# Amplifier.net
KiCad netlist of a schematic drawn in Altium Designer
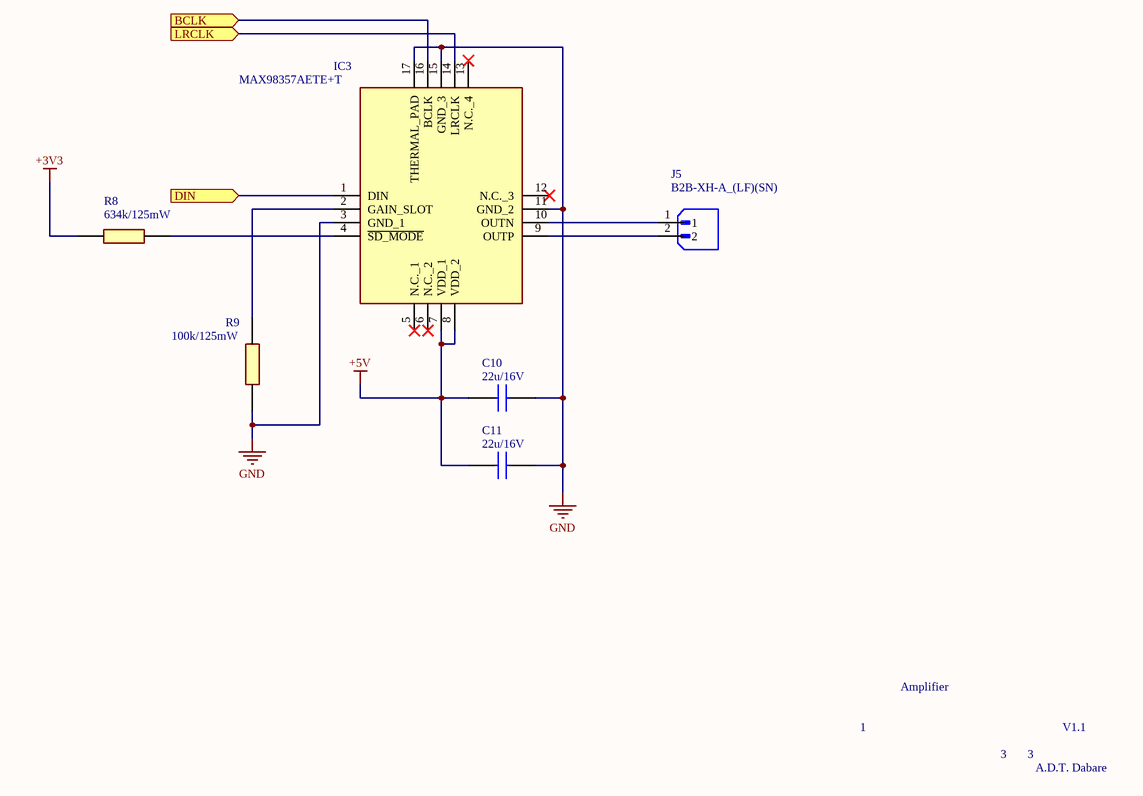
[diagram p0: Amplifier.SchDoc]

(export (version "E")
  (design (tool "Eeschema 10.0.6"))
  (components
    (comp (ref "C10")
      (value "22u/16V")
      (footprint "SamacSys:C0805")
      (description "Multilayer Ceramic Capacitors MLCC - SMD/SMT 16V 0.1uF X7R 0805 10% Flex AEC-Q200")
      (fields
        (field (name "MANUFACTURER_PART_NUMBER") "C0805X104K4RACAUTO")
        (field (name "MOUSER PART NUMBER") "80-C0805X104K4RAUTO")
      )
      (libsource (lib "*") (part "C0805X104K4RACAUTO"))
    )
    (comp (ref "C11")
      (value "22u/16V")
      (footprint "SamacSys:CAPC2012X94N")
      (fields
        (field (name "MANUFACTURER_PART_NUMBER") "0805YC106KAT2A")
        (field (name "MOUSER PART NUMBER") "581-0805YC106KAT2A")
      )
      (libsource (lib "*") (part "0805YC106KAT2A"))
    )
    (comp (ref "IC3")
      (value "MAX98357AETE+T")
      (footprint "SamacSys:QFN50P300X300X80-17N")
      (description "Audio Amplifiers Digital Input Class D Amplifier")
      (fields (field (name "MOUSER PART NUMBER") "700-MAX98357AETE+T"))
      (libsource (lib "*") (part "MAX98357AETE+T"))
    )
    (comp (ref "J5")
      (value "B2B-XH-A_(LF)(SN)")
      (footprint "JST_B2B-XH-A_(LF)(SN)")
      (description "Connector Header Through Hole 2 position 0.098 (2.50mm)")
      (fields (field (name "MF") "JST Sales") (field (name "MP") "B2B-XH-A (LF)(SN)"))
      (libsource (lib "B2B-XH-A__LF__SN_") (part "B2B-XH-A_(LF)(SN)"))
    )
    (comp (ref "R8")
      (value "634k/125mW")
      (footprint "SamacSys:RESC2012X50N")
      (description "Thick Film Resistors - SMD 1/8watt 634Kohms 1%")
      (fields
        (field (name "MANUFACTURER_PART_NUMBER") "CRCW0805634KFKEA")
        (field (name "MOUSER PART NUMBER") "71-CRCW0805634KFKEA")
      )
      (libsource (lib "*") (part "CRCW0805634KFKEA"))
    )
    (comp (ref "R9")
      (value "100k/125mW")
      (footprint "SamacSys:ERA6AEB101V")
      (description "Thin Film Resistors - SMD 0805 100Kohms 25ppm 0.5% AEC-Q200")
      (fields
        (field (name "MANUFACTURER_PART_NUMBER") "ERA-6AED104V")
        (field (name "MOUSER PART NUMBER") "667-ERA-6AED104V")
      )
      (libsource (lib "*") (part "ERA-6AED104V"))
    )
  )
  (nets
    (net (code "1") (name "+3V3") (class "Default")
      (node (ref "R8") (pin "1") (pinfunction "1_1") (pintype "passive"))
    )
    (net (code "2") (name "+5V") (class "Default")
      (node (ref "C10") (pin "1") (pinfunction "1_1") (pintype "passive"))
      (node (ref "C11") (pin "1") (pinfunction "1_1") (pintype "passive"))
      (node (ref "IC3") (pin "7") (pinfunction "VDD_1_7") (pintype "passive"))
      (node (ref "IC3") (pin "8") (pinfunction "VDD_2_8") (pintype "passive"))
    )
    (net (code "3") (name "/BCLK") (class "Default")
      (node (ref "IC3") (pin "16") (pinfunction "BCLK_16") (pintype "passive"))
    )
    (net (code "4") (name "/DIN") (class "Default")
      (node (ref "IC3") (pin "1") (pinfunction "DIN_1") (pintype "passive"))
    )
    (net (code "5") (name "/LRCLK") (class "Default")
      (node (ref "IC3") (pin "14") (pinfunction "LRCLK_14") (pintype "passive"))
    )
    (net (code "6") (name "GND") (class "Default")
      (node (ref "C10") (pin "2") (pinfunction "2_2") (pintype "passive"))
      (node (ref "C11") (pin "2") (pinfunction "2_2") (pintype "passive"))
      (node (ref "IC3") (pin "11") (pinfunction "GND_2_11") (pintype "passive"))
      (node (ref "IC3") (pin "15") (pinfunction "GND_3_15") (pintype "passive"))
      (node (ref "IC3") (pin "17") (pinfunction "THERMAL_PAD_17") (pintype "passive"))
      (node (ref "IC3") (pin "3") (pinfunction "GND_1_3") (pintype "passive"))
      (node (ref "R9") (pin "1") (pinfunction "1_1") (pintype "passive"))
    )
    (net (code "7") (name "Net-(IC3-GAIN_SLOT)") (class "Default")
      (node (ref "IC3") (pin "2") (pinfunction "GAIN_SLOT_2") (pintype "passive"))
      (node (ref "R9") (pin "2") (pinfunction "2_2") (pintype "passive"))
    )
    (net (code "8") (name "Net-(IC3-OUTN)") (class "Default")
      (node (ref "IC3") (pin "10") (pinfunction "OUTN_10") (pintype "passive"))
      (node (ref "J5") (pin "1") (pinfunction "1_1") (pintype "passive"))
    )
    (net (code "9") (name "Net-(IC3-OUTP)") (class "Default")
      (node (ref "IC3") (pin "9") (pinfunction "OUTP_9") (pintype "passive"))
      (node (ref "J5") (pin "2") (pinfunction "2_2") (pintype "passive"))
    )
    (net (code "10") (name "Net-(IC3-~{SD_MODE})") (class "Default")
      (node (ref "IC3") (pin "4") (pinfunction "~{SD_MODE}_4") (pintype "passive"))
      (node (ref "R8") (pin "2") (pinfunction "2_2") (pintype "passive"))
    )
    (net (code "11") (name "unconnected-(IC3-N.C._1-Pad5)") (class "Default")
      (node (ref "IC3") (pin "5") (pinfunction "N.C._1_5") (pintype "passive+no_connect"))
    )
    (net (code "12") (name "unconnected-(IC3-N.C._2-Pad6)") (class "Default")
      (node (ref "IC3") (pin "6") (pinfunction "N.C._2_6") (pintype "passive+no_connect"))
    )
    (net (code "13") (name "unconnected-(IC3-N.C._3-Pad12)") (class "Default")
      (node (ref "IC3") (pin "12") (pinfunction "N.C._3_12") (pintype "passive+no_connect"))
    )
    (net (code "14") (name "unconnected-(IC3-N.C._4-Pad13)") (class "Default")
      (node (ref "IC3") (pin "13") (pinfunction "N.C._4_13") (pintype "passive+no_connect"))
    )
  )
)
